# Main_Board_V2_0.net
KiCad netlist of a schematic drawn in EAGLE
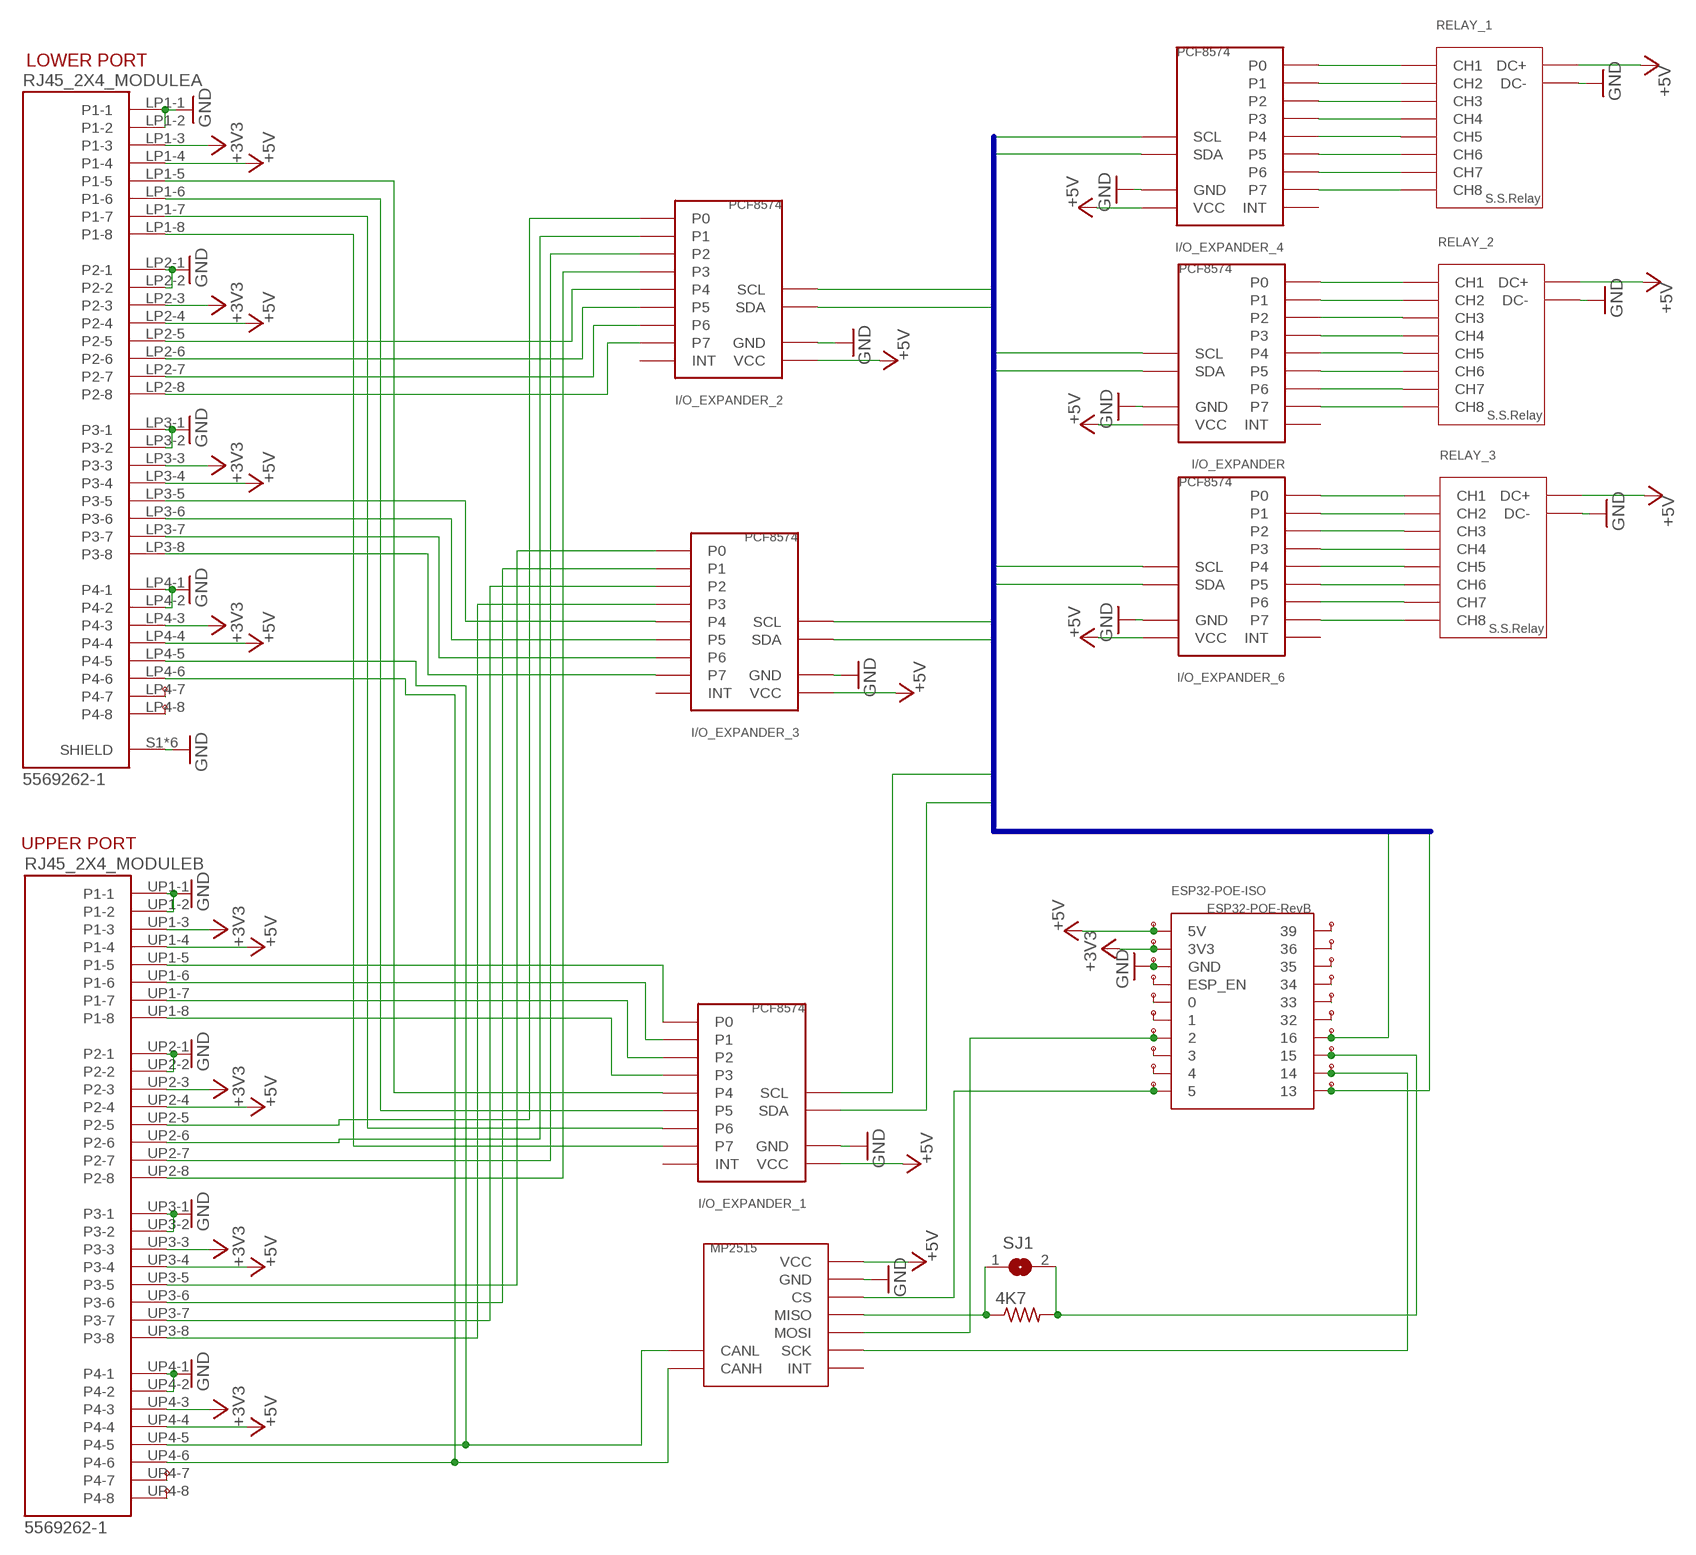
[diagram p0: schematic, sheet 1]

(export (version "E")
  (design (tool "Eeschema 10.0.6"))
  (components
    (comp (ref "4K7")
      (value "R-US_0207/10")
      (footprint "eagle-import:0207_10")
      (libsource (lib "eagle-import") (part "R-US_0207/10"))
    )
    (comp (ref "ESP32-POE-ISO")
      (value "ESP-POE")
      (footprint "eagle-import:ESP-POE")
      (libsource (lib "eagle-import") (part "ESP-POE"))
    )
    (comp (ref "I/O_EXPANDER")
      (value "PCF8574-MODULE_ESPELHADO")
      (footprint "eagle-import:PCF8574-MODULE_ESPELHADO")
      (libsource (lib "eagle-import") (part "PCF8574-MODULE_ESPELHADO"))
    )
    (comp (ref "I/O_EXPANDER_1")
      (value "PCF8574-MODULE_ESPELHADO")
      (footprint "eagle-import:PCF8574-MODULE_ESPELHADO")
      (libsource (lib "eagle-import") (part "PCF8574-MODULE_ESPELHADO"))
    )
    (comp (ref "I/O_EXPANDER_2")
      (value "PCF8574-MODULE_ESPELHADO")
      (footprint "eagle-import:PCF8574-MODULE_ESPELHADO")
      (libsource (lib "eagle-import") (part "PCF8574-MODULE_ESPELHADO"))
    )
    (comp (ref "I/O_EXPANDER_3")
      (value "PCF8574-MODULE_ESPELHADO")
      (footprint "eagle-import:PCF8574-MODULE_ESPELHADO")
      (libsource (lib "eagle-import") (part "PCF8574-MODULE_ESPELHADO"))
    )
    (comp (ref "I/O_EXPANDER_4")
      (value "PCF8574-MODULE_ESPELHADO")
      (footprint "eagle-import:PCF8574-MODULE_ESPELHADO")
      (libsource (lib "eagle-import") (part "PCF8574-MODULE_ESPELHADO"))
    )
    (comp (ref "I/O_EXPANDER_6")
      (value "PCF8574-MODULE_ESPELHADO")
      (footprint "eagle-import:PCF8574-MODULE_ESPELHADO")
      (libsource (lib "eagle-import") (part "PCF8574-MODULE_ESPELHADO"))
    )
    (comp (ref "RELAY_1")
      (value "SSR_M_FULL_SEM_LIGACOES")
      (footprint "eagle-import:SSR_M_SEM_LIGACOES")
      (libsource (lib "eagle-import") (part "SSR_M_FULL_SEM_LIGACOES"))
    )
    (comp (ref "RELAY_2")
      (value "SSR_M_FULL_SEM_LIGACOES")
      (footprint "eagle-import:SSR_M_SEM_LIGACOES")
      (libsource (lib "eagle-import") (part "SSR_M_FULL_SEM_LIGACOES"))
    )
    (comp (ref "RELAY_3")
      (value "SSR_M_FULL_SEM_LIGACOES")
      (footprint "eagle-import:SSR_M_SEM_LIGACOES")
      (libsource (lib "eagle-import") (part "SSR_M_FULL_SEM_LIGACOES"))
    )
    (comp (ref "RJ45_2X4_MODULE")
      (value "5569262-1")
      (footprint "eagle-import:TE_5569262-1")
      (fields (field (name "MF") "TE Connectivity"))
      (libsource (lib "eagle-import") (part "5569262-1"))
    )
    (comp (ref "SJ1") (value "SJ") (footprint "eagle-import:SJ") (libsource (lib "eagle-import") (part "SJ")))
    (comp (ref "U$1") (value "TP") (footprint "eagle-import:TP") (libsource (lib "eagle-import") (part "TP")))
    (comp (ref "U$2") (value "TP") (footprint "eagle-import:TP") (libsource (lib "eagle-import") (part "TP")))
    (comp (ref "U$4") (value "TP") (footprint "eagle-import:TP") (libsource (lib "eagle-import") (part "TP")))
    (comp (ref "U$5") (value "TP") (footprint "eagle-import:TP") (libsource (lib "eagle-import") (part "TP")))
    (comp (ref "U$6") (value "TP") (footprint "eagle-import:TP") (libsource (lib "eagle-import") (part "TP")))
    (comp (ref "U$7") (value "TP") (footprint "eagle-import:TP") (libsource (lib "eagle-import") (part "TP")))
    (comp (ref "U$8") (value "TP") (footprint "eagle-import:TP") (libsource (lib "eagle-import") (part "TP")))
    (comp (ref "U$9") (value "TP") (footprint "eagle-import:TP") (libsource (lib "eagle-import") (part "TP")))
    (comp (ref "U$10")
      (value "TP")
      (footprint "eagle-import:TP")
      (libsource (lib "eagle-import") (part "TP"))
    )
    (comp (ref "U$11")
      (value "TP")
      (footprint "eagle-import:TP")
      (libsource (lib "eagle-import") (part "TP"))
    )
    (comp (ref "U$12")
      (value "TP")
      (footprint "eagle-import:TP")
      (libsource (lib "eagle-import") (part "TP"))
    )
    (comp (ref "U$13")
      (value "TP")
      (footprint "eagle-import:TP")
      (libsource (lib "eagle-import") (part "TP"))
    )
    (comp (ref "U$14")
      (value "TP")
      (footprint "eagle-import:TP")
      (libsource (lib "eagle-import") (part "TP"))
    )
    (comp (ref "U$15")
      (value "TP")
      (footprint "eagle-import:TP")
      (libsource (lib "eagle-import") (part "TP"))
    )
    (comp (ref "U$16")
      (value "TP")
      (footprint "eagle-import:TP")
      (libsource (lib "eagle-import") (part "TP"))
    )
    (comp (ref "U$17")
      (value "TP")
      (footprint "eagle-import:TP")
      (libsource (lib "eagle-import") (part "TP"))
    )
    (comp (ref "U$18")
      (value "TP")
      (footprint "eagle-import:TP")
      (libsource (lib "eagle-import") (part "TP"))
    )
    (comp (ref "U$19")
      (value "TP")
      (footprint "eagle-import:TP")
      (libsource (lib "eagle-import") (part "TP"))
    )
    (comp (ref "U$20")
      (value "TP")
      (footprint "eagle-import:TP")
      (libsource (lib "eagle-import") (part "TP"))
    )
    (comp (ref "U$21")
      (value "TP")
      (footprint "eagle-import:TP")
      (libsource (lib "eagle-import") (part "TP"))
    )
    (comp (ref "U$22")
      (value "TP")
      (footprint "eagle-import:TP")
      (libsource (lib "eagle-import") (part "TP"))
    )
    (comp (ref "U$23")
      (value "TP")
      (footprint "eagle-import:TP")
      (libsource (lib "eagle-import") (part "TP"))
    )
    (comp (ref "U$24")
      (value "TP")
      (footprint "eagle-import:TP")
      (libsource (lib "eagle-import") (part "TP"))
    )
    (comp (ref "U$25")
      (value "TP")
      (footprint "eagle-import:TP")
      (libsource (lib "eagle-import") (part "TP"))
    )
    (comp (ref "U$26")
      (value "MCP2515_MODULE_SEM_LIGACOES")
      (footprint "eagle-import:MCP2515_MODULE_SEM_LIGACOES")
      (libsource (lib "eagle-import") (part "MCP2515_MODULE_SEM_LIGACOES"))
    )
  )
  (nets
    (net (code "1") (name "+3V3") (class "Default")
      (node (ref "ESP32-POE-ISO") (pin "3V3") (pinfunction "3V3_3V3") (pintype "bidirectional"))
      (node (ref "RJ45_2X4_MODULE") (pin "LP1-3") (pinfunction "P1-3_LP1-3") (pintype "passive"))
      (node (ref "RJ45_2X4_MODULE") (pin "LP2-3") (pinfunction "P2-3_LP2-3") (pintype "passive"))
      (node (ref "RJ45_2X4_MODULE") (pin "LP3-3") (pinfunction "P3-3_LP3-3") (pintype "passive"))
      (node (ref "RJ45_2X4_MODULE") (pin "LP4-3") (pinfunction "P4-3_LP4-3") (pintype "passive"))
      (node (ref "RJ45_2X4_MODULE") (pin "UP1-3") (pinfunction "P1-3_UP1-3") (pintype "passive"))
      (node (ref "RJ45_2X4_MODULE") (pin "UP2-3") (pinfunction "P2-3_UP2-3") (pintype "passive"))
      (node (ref "RJ45_2X4_MODULE") (pin "UP3-3") (pinfunction "P3-3_UP3-3") (pintype "passive"))
      (node (ref "RJ45_2X4_MODULE") (pin "UP4-3") (pinfunction "P4-3_UP4-3") (pintype "passive"))
      (node (ref "U$6") (pin "P$1") (pinfunction "P$1_P$1") (pintype "bidirectional"))
    )
    (net (code "2") (name "+5V") (class "Default")
      (node (ref "ESP32-POE-ISO") (pin "5V") (pinfunction "5V_5V") (pintype "bidirectional"))
      (node (ref "I/O_EXPANDER") (pin "VCC") (pinfunction "VCC_VCC") (pintype "bidirectional"))
      (node (ref "I/O_EXPANDER_1") (pin "VCC") (pinfunction "VCC_VCC") (pintype "bidirectional"))
      (node (ref "I/O_EXPANDER_2") (pin "VCC") (pinfunction "VCC_VCC") (pintype "bidirectional"))
      (node (ref "I/O_EXPANDER_3") (pin "VCC") (pinfunction "VCC_VCC") (pintype "bidirectional"))
      (node (ref "I/O_EXPANDER_4") (pin "VCC") (pinfunction "VCC_VCC") (pintype "bidirectional"))
      (node (ref "I/O_EXPANDER_6") (pin "VCC") (pinfunction "VCC_VCC") (pintype "bidirectional"))
      (node (ref "RELAY_1") (pin "DC+") (pinfunction "DC+_DC+") (pintype "bidirectional"))
      (node (ref "RELAY_2") (pin "DC+") (pinfunction "DC+_DC+") (pintype "bidirectional"))
      (node (ref "RELAY_3") (pin "DC+") (pinfunction "DC+_DC+") (pintype "bidirectional"))
      (node (ref "RJ45_2X4_MODULE") (pin "LP1-4") (pinfunction "P1-4_LP1-4") (pintype "passive"))
      (node (ref "RJ45_2X4_MODULE") (pin "LP2-4") (pinfunction "P2-4_LP2-4") (pintype "passive"))
      (node (ref "RJ45_2X4_MODULE") (pin "LP3-4") (pinfunction "P3-4_LP3-4") (pintype "passive"))
      (node (ref "RJ45_2X4_MODULE") (pin "LP4-4") (pinfunction "P4-4_LP4-4") (pintype "passive"))
      (node (ref "RJ45_2X4_MODULE") (pin "UP1-4") (pinfunction "P1-4_UP1-4") (pintype "passive"))
      (node (ref "RJ45_2X4_MODULE") (pin "UP2-4") (pinfunction "P2-4_UP2-4") (pintype "passive"))
      (node (ref "RJ45_2X4_MODULE") (pin "UP3-4") (pinfunction "P3-4_UP3-4") (pintype "passive"))
      (node (ref "RJ45_2X4_MODULE") (pin "UP4-4") (pinfunction "P4-4_UP4-4") (pintype "passive"))
      (node (ref "U$2") (pin "P$1") (pinfunction "P$1_P$1") (pintype "bidirectional"))
      (node (ref "U$26") (pin "VCC") (pinfunction "VCC_VCC") (pintype "bidirectional"))
    )
    (net (code "3") (name "/SCL") (class "Default")
      (node (ref "ESP32-POE-ISO") (pin "16") (pinfunction "16_16") (pintype "bidirectional"))
      (node (ref "I/O_EXPANDER") (pin "SCL") (pinfunction "SCL_SCL") (pintype "bidirectional"))
      (node (ref "I/O_EXPANDER_1") (pin "SCL") (pinfunction "SCL_SCL") (pintype "bidirectional"))
      (node (ref "I/O_EXPANDER_2") (pin "SCL") (pinfunction "SCL_SCL") (pintype "bidirectional"))
      (node (ref "I/O_EXPANDER_3") (pin "SCL") (pinfunction "SCL_SCL") (pintype "bidirectional"))
      (node (ref "I/O_EXPANDER_4") (pin "SCL") (pinfunction "SCL_SCL") (pintype "bidirectional"))
      (node (ref "I/O_EXPANDER_6") (pin "SCL") (pinfunction "SCL_SCL") (pintype "bidirectional"))
      (node (ref "U$21") (pin "P$1") (pinfunction "P$1_P$1") (pintype "bidirectional"))
    )
    (net (code "4") (name "/SDA") (class "Default")
      (node (ref "ESP32-POE-ISO") (pin "13") (pinfunction "13_13") (pintype "bidirectional"))
      (node (ref "I/O_EXPANDER") (pin "SDA") (pinfunction "SDA_SDA") (pintype "bidirectional"))
      (node (ref "I/O_EXPANDER_1") (pin "SDA") (pinfunction "SDA_SDA") (pintype "bidirectional"))
      (node (ref "I/O_EXPANDER_2") (pin "SDA") (pinfunction "SDA_SDA") (pintype "bidirectional"))
      (node (ref "I/O_EXPANDER_3") (pin "SDA") (pinfunction "SDA_SDA") (pintype "bidirectional"))
      (node (ref "I/O_EXPANDER_4") (pin "SDA") (pinfunction "SDA_SDA") (pintype "bidirectional"))
      (node (ref "I/O_EXPANDER_6") (pin "SDA") (pinfunction "SDA_SDA") (pintype "bidirectional"))
      (node (ref "U$24") (pin "P$1") (pinfunction "P$1_P$1") (pintype "bidirectional"))
    )
    (net (code "5") (name "GND") (class "Default")
      (node (ref "ESP32-POE-ISO") (pin "GND") (pinfunction "GND_GND") (pintype "bidirectional"))
      (node (ref "I/O_EXPANDER") (pin "GND") (pinfunction "GND_GND") (pintype "bidirectional"))
      (node (ref "I/O_EXPANDER_1") (pin "GND") (pinfunction "GND_GND") (pintype "bidirectional"))
      (node (ref "I/O_EXPANDER_2") (pin "GND") (pinfunction "GND_GND") (pintype "bidirectional"))
      (node (ref "I/O_EXPANDER_3") (pin "GND") (pinfunction "GND_GND") (pintype "bidirectional"))
      (node (ref "I/O_EXPANDER_4") (pin "GND") (pinfunction "GND_GND") (pintype "bidirectional"))
      (node (ref "I/O_EXPANDER_6") (pin "GND") (pinfunction "GND_GND") (pintype "bidirectional"))
      (node (ref "RELAY_1") (pin "DC-") (pinfunction "DC-_DC-") (pintype "bidirectional"))
      (node (ref "RELAY_2") (pin "DC-") (pinfunction "DC-_DC-") (pintype "bidirectional"))
      (node (ref "RELAY_3") (pin "DC-") (pinfunction "DC-_DC-") (pintype "bidirectional"))
      (node (ref "RJ45_2X4_MODULE") (pin "LP1-1") (pinfunction "P1-1_LP1-1") (pintype "passive"))
      (node (ref "RJ45_2X4_MODULE") (pin "LP1-2") (pinfunction "P1-2_LP1-2") (pintype "passive"))
      (node (ref "RJ45_2X4_MODULE") (pin "LP2-1") (pinfunction "P2-1_LP2-1") (pintype "passive"))
      (node (ref "RJ45_2X4_MODULE") (pin "LP2-2") (pinfunction "P2-2_LP2-2") (pintype "passive"))
      (node (ref "RJ45_2X4_MODULE") (pin "LP3-1") (pinfunction "P3-1_LP3-1") (pintype "passive"))
      (node (ref "RJ45_2X4_MODULE") (pin "LP3-2") (pinfunction "P3-2_LP3-2") (pintype "passive"))
      (node (ref "RJ45_2X4_MODULE") (pin "LP4-1") (pinfunction "P4-1_LP4-1") (pintype "passive"))
      (node (ref "RJ45_2X4_MODULE") (pin "LP4-2") (pinfunction "P4-2_LP4-2") (pintype "passive"))
      (node (ref "RJ45_2X4_MODULE") (pin "S1") (pinfunction "SHIELD_S1") (pintype "passive"))
      (node (ref "RJ45_2X4_MODULE") (pin "S2") (pinfunction "SHIELD_S2") (pintype "passive"))
      (node (ref "RJ45_2X4_MODULE") (pin "S3") (pinfunction "SHIELD_S3") (pintype "passive"))
      (node (ref "RJ45_2X4_MODULE") (pin "S4") (pinfunction "SHIELD_S4") (pintype "passive"))
      (node (ref "RJ45_2X4_MODULE") (pin "S5") (pinfunction "SHIELD_S5") (pintype "passive"))
      (node (ref "RJ45_2X4_MODULE") (pin "S6") (pinfunction "SHIELD_S6") (pintype "passive"))
      (node (ref "RJ45_2X4_MODULE") (pin "UP1-1") (pinfunction "P1-1_UP1-1") (pintype "passive"))
      (node (ref "RJ45_2X4_MODULE") (pin "UP1-2") (pinfunction "P1-2_UP1-2") (pintype "passive"))
      (node (ref "RJ45_2X4_MODULE") (pin "UP2-1") (pinfunction "P2-1_UP2-1") (pintype "passive"))
      (node (ref "RJ45_2X4_MODULE") (pin "UP2-2") (pinfunction "P2-2_UP2-2") (pintype "passive"))
      (node (ref "RJ45_2X4_MODULE") (pin "UP3-1") (pinfunction "P3-1_UP3-1") (pintype "passive"))
      (node (ref "RJ45_2X4_MODULE") (pin "UP3-2") (pinfunction "P3-2_UP3-2") (pintype "passive"))
      (node (ref "RJ45_2X4_MODULE") (pin "UP4-1") (pinfunction "P4-1_UP4-1") (pintype "passive"))
      (node (ref "RJ45_2X4_MODULE") (pin "UP4-2") (pinfunction "P4-2_UP4-2") (pintype "passive"))
      (node (ref "U$26") (pin "GND") (pinfunction "GND_GND") (pintype "bidirectional"))
      (node (ref "U$7") (pin "P$1") (pinfunction "P$1_P$1") (pintype "bidirectional"))
    )
    (net (code "6") (name "Net-(4K7-Pad1)") (class "Default")
      (node (ref "4K7") (pin "1") (pinfunction "1_1") (pintype "passive"))
      (node (ref "SJ1") (pin "1") (pinfunction "1_1") (pintype "passive"))
      (node (ref "U$26") (pin "MISO") (pinfunction "MISO_MISO") (pintype "bidirectional"))
    )
    (net (code "7") (name "Net-(4K7-Pad2)") (class "Default")
      (node (ref "4K7") (pin "2") (pinfunction "2_2") (pintype "passive"))
      (node (ref "ESP32-POE-ISO") (pin "15") (pinfunction "15_15") (pintype "bidirectional"))
      (node (ref "SJ1") (pin "2") (pinfunction "2_2") (pintype "passive"))
      (node (ref "U$22") (pin "P$1") (pinfunction "P$1_P$1") (pintype "bidirectional"))
    )
    (net (code "8") (name "Net-(ESP32-POE-ISO-Pad0)") (class "Default")
      (node (ref "ESP32-POE-ISO") (pin "0") (pinfunction "0_0") (pintype "bidirectional"))
      (node (ref "U$9") (pin "P$1") (pinfunction "P$1_P$1") (pintype "bidirectional"))
    )
    (net (code "9") (name "Net-(ESP32-POE-ISO-Pad1)") (class "Default")
      (node (ref "ESP32-POE-ISO") (pin "1") (pinfunction "1_1") (pintype "bidirectional"))
      (node (ref "U$10") (pin "P$1") (pinfunction "P$1_P$1") (pintype "bidirectional"))
    )
    (net (code "10") (name "Net-(ESP32-POE-ISO-Pad2)") (class "Default")
      (node (ref "ESP32-POE-ISO") (pin "2") (pinfunction "2_2") (pintype "bidirectional"))
      (node (ref "U$11") (pin "P$1") (pinfunction "P$1_P$1") (pintype "bidirectional"))
      (node (ref "U$26") (pin "MOSI") (pinfunction "MOSI_MOSI") (pintype "bidirectional"))
    )
    (net (code "11") (name "Net-(ESP32-POE-ISO-Pad3)") (class "Default")
      (node (ref "ESP32-POE-ISO") (pin "3") (pinfunction "3_3") (pintype "bidirectional"))
      (node (ref "U$12") (pin "P$1") (pinfunction "P$1_P$1") (pintype "bidirectional"))
    )
    (net (code "12") (name "Net-(ESP32-POE-ISO-Pad4)") (class "Default")
      (node (ref "ESP32-POE-ISO") (pin "4") (pinfunction "4_4") (pintype "bidirectional"))
      (node (ref "U$13") (pin "P$1") (pinfunction "P$1_P$1") (pintype "bidirectional"))
    )
    (net (code "13") (name "Net-(ESP32-POE-ISO-Pad5)") (class "Default")
      (node (ref "ESP32-POE-ISO") (pin "5") (pinfunction "5_5") (pintype "bidirectional"))
      (node (ref "U$14") (pin "P$1") (pinfunction "P$1_P$1") (pintype "bidirectional"))
      (node (ref "U$26") (pin "CS") (pinfunction "CS_CS") (pintype "bidirectional"))
    )
    (net (code "14") (name "Net-(ESP32-POE-ISO-Pad14)") (class "Default")
      (node (ref "ESP32-POE-ISO") (pin "14") (pinfunction "14_14") (pintype "bidirectional"))
      (node (ref "U$23") (pin "P$1") (pinfunction "P$1_P$1") (pintype "bidirectional"))
      (node (ref "U$26") (pin "SCK") (pinfunction "SCK_SCK") (pintype "bidirectional"))
    )
    (net (code "15") (name "Net-(ESP32-POE-ISO-Pad32)") (class "Default")
      (node (ref "ESP32-POE-ISO") (pin "32") (pinfunction "32_32") (pintype "bidirectional"))
      (node (ref "U$20") (pin "P$1") (pinfunction "P$1_P$1") (pintype "bidirectional"))
    )
    (net (code "16") (name "Net-(ESP32-POE-ISO-Pad33)") (class "Default")
      (node (ref "ESP32-POE-ISO") (pin "33") (pinfunction "33_33") (pintype "bidirectional"))
      (node (ref "U$19") (pin "P$1") (pinfunction "P$1_P$1") (pintype "bidirectional"))
    )
    (net (code "17") (name "Net-(ESP32-POE-ISO-Pad34)") (class "Default")
      (node (ref "ESP32-POE-ISO") (pin "34") (pinfunction "34_34") (pintype "bidirectional"))
      (node (ref "U$18") (pin "P$1") (pinfunction "P$1_P$1") (pintype "bidirectional"))
    )
    (net (code "18") (name "Net-(ESP32-POE-ISO-Pad35)") (class "Default")
      (node (ref "ESP32-POE-ISO") (pin "35") (pinfunction "35_35") (pintype "bidirectional"))
      (node (ref "U$17") (pin "P$1") (pinfunction "P$1_P$1") (pintype "bidirectional"))
    )
    (net (code "19") (name "Net-(ESP32-POE-ISO-Pad36)") (class "Default")
      (node (ref "ESP32-POE-ISO") (pin "36") (pinfunction "36_36") (pintype "bidirectional"))
      (node (ref "U$16") (pin "P$1") (pinfunction "P$1_P$1") (pintype "bidirectional"))
    )
    (net (code "20") (name "Net-(ESP32-POE-ISO-Pad39)") (class "Default")
      (node (ref "ESP32-POE-ISO") (pin "39") (pinfunction "39_39") (pintype "bidirectional"))
      (node (ref "U$15") (pin "P$1") (pinfunction "P$1_P$1") (pintype "bidirectional"))
    )
    (net (code "21") (name "Net-(ESP32-POE-ISO-PadESP_EN)") (class "Default")
      (node (ref "ESP32-POE-ISO") (pin "ESP_EN") (pinfunction "ESP_EN_ESP_EN") (pintype "bidirectional"))
      (node (ref "U$8") (pin "P$1") (pinfunction "P$1_P$1") (pintype "bidirectional"))
    )
    (net (code "22") (name "Net-(I/O_EXPANDER-PadP0)") (class "Default")
      (node (ref "I/O_EXPANDER") (pin "P0") (pinfunction "P0_P0") (pintype "bidirectional"))
      (node (ref "RELAY_2") (pin "CH1") (pinfunction "CH1_CH1") (pintype "bidirectional"))
    )
    (net (code "23") (name "Net-(I/O_EXPANDER-PadP1)") (class "Default")
      (node (ref "I/O_EXPANDER") (pin "P1") (pinfunction "P1_P1") (pintype "bidirectional"))
      (node (ref "RELAY_2") (pin "CH2") (pinfunction "CH2_CH2") (pintype "bidirectional"))
    )
    (net (code "24") (name "Net-(I/O_EXPANDER-PadP2)") (class "Default")
      (node (ref "I/O_EXPANDER") (pin "P2") (pinfunction "P2_P2") (pintype "bidirectional"))
      (node (ref "RELAY_2") (pin "CH3") (pinfunction "CH3_CH3") (pintype "bidirectional"))
    )
    (net (code "25") (name "Net-(I/O_EXPANDER-PadP3)") (class "Default")
      (node (ref "I/O_EXPANDER") (pin "P3") (pinfunction "P3_P3") (pintype "bidirectional"))
      (node (ref "RELAY_2") (pin "CH4") (pinfunction "CH4_CH4") (pintype "bidirectional"))
    )
    (net (code "26") (name "Net-(I/O_EXPANDER-PadP4)") (class "Default")
      (node (ref "I/O_EXPANDER") (pin "P4") (pinfunction "P4_P4") (pintype "bidirectional"))
      (node (ref "RELAY_2") (pin "CH5") (pinfunction "CH5_CH5") (pintype "bidirectional"))
    )
    (net (code "27") (name "Net-(I/O_EXPANDER-PadP5)") (class "Default")
      (node (ref "I/O_EXPANDER") (pin "P5") (pinfunction "P5_P5") (pintype "bidirectional"))
      (node (ref "RELAY_2") (pin "CH6") (pinfunction "CH6_CH6") (pintype "bidirectional"))
    )
    (net (code "28") (name "Net-(I/O_EXPANDER-PadP6)") (class "Default")
      (node (ref "I/O_EXPANDER") (pin "P6") (pinfunction "P6_P6") (pintype "bidirectional"))
      (node (ref "RELAY_2") (pin "CH7") (pinfunction "CH7_CH7") (pintype "bidirectional"))
    )
    (net (code "29") (name "Net-(I/O_EXPANDER-PadP7)") (class "Default")
      (node (ref "I/O_EXPANDER") (pin "P7") (pinfunction "P7_P7") (pintype "bidirectional"))
      (node (ref "RELAY_2") (pin "CH8") (pinfunction "CH8_CH8") (pintype "bidirectional"))
    )
    (net (code "30") (name "Net-(I/O_EXPANDER_4-PadP0)") (class "Default")
      (node (ref "I/O_EXPANDER_4") (pin "P0") (pinfunction "P0_P0") (pintype "bidirectional"))
      (node (ref "RELAY_1") (pin "CH1") (pinfunction "CH1_CH1") (pintype "bidirectional"))
    )
    (net (code "31") (name "Net-(I/O_EXPANDER_4-PadP1)") (class "Default")
      (node (ref "I/O_EXPANDER_4") (pin "P1") (pinfunction "P1_P1") (pintype "bidirectional"))
      (node (ref "RELAY_1") (pin "CH2") (pinfunction "CH2_CH2") (pintype "bidirectional"))
    )
    (net (code "32") (name "Net-(I/O_EXPANDER_4-PadP2)") (class "Default")
      (node (ref "I/O_EXPANDER_4") (pin "P2") (pinfunction "P2_P2") (pintype "bidirectional"))
      (node (ref "RELAY_1") (pin "CH3") (pinfunction "CH3_CH3") (pintype "bidirectional"))
    )
    (net (code "33") (name "Net-(I/O_EXPANDER_4-PadP3)") (class "Default")
      (node (ref "I/O_EXPANDER_4") (pin "P3") (pinfunction "P3_P3") (pintype "bidirectional"))
      (node (ref "RELAY_1") (pin "CH4") (pinfunction "CH4_CH4") (pintype "bidirectional"))
    )
    (net (code "34") (name "Net-(I/O_EXPANDER_4-PadP4)") (class "Default")
      (node (ref "I/O_EXPANDER_4") (pin "P4") (pinfunction "P4_P4") (pintype "bidirectional"))
      (node (ref "RELAY_1") (pin "CH5") (pinfunction "CH5_CH5") (pintype "bidirectional"))
    )
    (net (code "35") (name "Net-(I/O_EXPANDER_4-PadP5)") (class "Default")
      (node (ref "I/O_EXPANDER_4") (pin "P5") (pinfunction "P5_P5") (pintype "bidirectional"))
      (node (ref "RELAY_1") (pin "CH6") (pinfunction "CH6_CH6") (pintype "bidirectional"))
    )
    (net (code "36") (name "Net-(I/O_EXPANDER_4-PadP6)") (class "Default")
      (node (ref "I/O_EXPANDER_4") (pin "P6") (pinfunction "P6_P6") (pintype "bidirectional"))
      (node (ref "RELAY_1") (pin "CH7") (pinfunction "CH7_CH7") (pintype "bidirectional"))
    )
    (net (code "37") (name "Net-(I/O_EXPANDER_4-PadP7)") (class "Default")
      (node (ref "I/O_EXPANDER_4") (pin "P7") (pinfunction "P7_P7") (pintype "bidirectional"))
      (node (ref "RELAY_1") (pin "CH8") (pinfunction "CH8_CH8") (pintype "bidirectional"))
    )
    (net (code "38") (name "Net-(I/O_EXPANDER_6-PadP0)") (class "Default")
      (node (ref "I/O_EXPANDER_6") (pin "P0") (pinfunction "P0_P0") (pintype "bidirectional"))
      (node (ref "RELAY_3") (pin "CH1") (pinfunction "CH1_CH1") (pintype "bidirectional"))
    )
    (net (code "39") (name "Net-(I/O_EXPANDER_6-PadP1)") (class "Default")
      (node (ref "I/O_EXPANDER_6") (pin "P1") (pinfunction "P1_P1") (pintype "bidirectional"))
      (node (ref "RELAY_3") (pin "CH2") (pinfunction "CH2_CH2") (pintype "bidirectional"))
    )
    (net (code "40") (name "Net-(I/O_EXPANDER_6-PadP2)") (class "Default")
      (node (ref "I/O_EXPANDER_6") (pin "P2") (pinfunction "P2_P2") (pintype "bidirectional"))
      (node (ref "RELAY_3") (pin "CH3") (pinfunction "CH3_CH3") (pintype "bidirectional"))
    )
    (net (code "41") (name "Net-(I/O_EXPANDER_6-PadP3)") (class "Default")
      (node (ref "I/O_EXPANDER_6") (pin "P3") (pinfunction "P3_P3") (pintype "bidirectional"))
      (node (ref "RELAY_3") (pin "CH4") (pinfunction "CH4_CH4") (pintype "bidirectional"))
    )
    (net (code "42") (name "Net-(I/O_EXPANDER_6-PadP4)") (class "Default")
      (node (ref "I/O_EXPANDER_6") (pin "P4") (pinfunction "P4_P4") (pintype "bidirectional"))
      (node (ref "RELAY_3") (pin "CH5") (pinfunction "CH5_CH5") (pintype "bidirectional"))
    )
    (net (code "43") (name "Net-(I/O_EXPANDER_6-PadP5)") (class "Default")
      (node (ref "I/O_EXPANDER_6") (pin "P5") (pinfunction "P5_P5") (pintype "bidirectional"))
      (node (ref "RELAY_3") (pin "CH6") (pinfunction "CH6_CH6") (pintype "bidirectional"))
    )
    (net (code "44") (name "Net-(I/O_EXPANDER_6-PadP6)") (class "Default")
      (node (ref "I/O_EXPANDER_6") (pin "P6") (pinfunction "P6_P6") (pintype "bidirectional"))
      (node (ref "RELAY_3") (pin "CH7") (pinfunction "CH7_CH7") (pintype "bidirectional"))
    )
    (net (code "45") (name "Net-(I/O_EXPANDER_6-PadP7)") (class "Default")
      (node (ref "I/O_EXPANDER_6") (pin "P7") (pinfunction "P7_P7") (pintype "bidirectional"))
      (node (ref "RELAY_3") (pin "CH8") (pinfunction "CH8_CH8") (pintype "bidirectional"))
    )
    (net (code "46") (name "Net-(RJ45_2X4_MODULEA-P1-5)") (class "Default")
      (node (ref "I/O_EXPANDER_1") (pin "P4") (pinfunction "P4_P4") (pintype "bidirectional"))
      (node (ref "RJ45_2X4_MODULE") (pin "LP1-5") (pinfunction "P1-5_LP1-5") (pintype "passive"))
    )
    (net (code "47") (name "Net-(RJ45_2X4_MODULEA-P1-6)") (class "Default")
      (node (ref "I/O_EXPANDER_1") (pin "P5") (pinfunction "P5_P5") (pintype "bidirectional"))
      (node (ref "RJ45_2X4_MODULE") (pin "LP1-6") (pinfunction "P1-6_LP1-6") (pintype "passive"))
    )
    (net (code "48") (name "Net-(RJ45_2X4_MODULEA-P1-7)") (class "Default")
      (node (ref "I/O_EXPANDER_1") (pin "P6") (pinfunction "P6_P6") (pintype "bidirectional"))
      (node (ref "RJ45_2X4_MODULE") (pin "LP1-7") (pinfunction "P1-7_LP1-7") (pintype "passive"))
    )
    (net (code "49") (name "Net-(RJ45_2X4_MODULEA-P1-8)") (class "Default")
      (node (ref "I/O_EXPANDER_1") (pin "P7") (pinfunction "P7_P7") (pintype "bidirectional"))
      (node (ref "RJ45_2X4_MODULE") (pin "LP1-8") (pinfunction "P1-8_LP1-8") (pintype "passive"))
    )
    (net (code "50") (name "Net-(RJ45_2X4_MODULEA-P2-5)") (class "Default")
      (node (ref "I/O_EXPANDER_2") (pin "P4") (pinfunction "P4_P4") (pintype "bidirectional"))
      (node (ref "RJ45_2X4_MODULE") (pin "LP2-5") (pinfunction "P2-5_LP2-5") (pintype "passive"))
    )
    (net (code "51") (name "Net-(RJ45_2X4_MODULEA-P2-6)") (class "Default")
      (node (ref "I/O_EXPANDER_2") (pin "P5") (pinfunction "P5_P5") (pintype "bidirectional"))
      (node (ref "RJ45_2X4_MODULE") (pin "LP2-6") (pinfunction "P2-6_LP2-6") (pintype "passive"))
    )
    (net (code "52") (name "Net-(RJ45_2X4_MODULEA-P2-7)") (class "Default")
      (node (ref "I/O_EXPANDER_2") (pin "P6") (pinfunction "P6_P6") (pintype "bidirectional"))
      (node (ref "RJ45_2X4_MODULE") (pin "LP2-7") (pinfunction "P2-7_LP2-7") (pintype "passive"))
    )
    (net (code "53") (name "Net-(RJ45_2X4_MODULEA-P2-8)") (class "Default")
      (node (ref "I/O_EXPANDER_2") (pin "P7") (pinfunction "P7_P7") (pintype "bidirectional"))
      (node (ref "RJ45_2X4_MODULE") (pin "LP2-8") (pinfunction "P2-8_LP2-8") (pintype "passive"))
    )
    (net (code "54") (name "Net-(RJ45_2X4_MODULEA-P3-5)") (class "Default")
      (node (ref "I/O_EXPANDER_3") (pin "P4") (pinfunction "P4_P4") (pintype "bidirectional"))
      (node (ref "RJ45_2X4_MODULE") (pin "LP3-5") (pinfunction "P3-5_LP3-5") (pintype "passive"))
    )
    (net (code "55") (name "Net-(RJ45_2X4_MODULEA-P3-6)") (class "Default")
      (node (ref "I/O_EXPANDER_3") (pin "P5") (pinfunction "P5_P5") (pintype "bidirectional"))
      (node (ref "RJ45_2X4_MODULE") (pin "LP3-6") (pinfunction "P3-6_LP3-6") (pintype "passive"))
    )
    (net (code "56") (name "Net-(RJ45_2X4_MODULEA-P3-7)") (class "Default")
      (node (ref "I/O_EXPANDER_3") (pin "P6") (pinfunction "P6_P6") (pintype "bidirectional"))
      (node (ref "RJ45_2X4_MODULE") (pin "LP3-7") (pinfunction "P3-7_LP3-7") (pintype "passive"))
    )
    (net (code "57") (name "Net-(RJ45_2X4_MODULEA-P3-8)") (class "Default")
      (node (ref "I/O_EXPANDER_3") (pin "P7") (pinfunction "P7_P7") (pintype "bidirectional"))
      (node (ref "RJ45_2X4_MODULE") (pin "LP3-8") (pinfunction "P3-8_LP3-8") (pintype "passive"))
    )
    (net (code "58") (name "Net-(RJ45_2X4_MODULEA-P4-5)") (class "Default")
      (node (ref "RJ45_2X4_MODULE") (pin "LP4-5") (pinfunction "P4-5_LP4-5") (pintype "passive"))
      (node (ref "RJ45_2X4_MODULE") (pin "UP4-5") (pinfunction "P4-5_UP4-5") (pintype "passive"))
      (node (ref "U$26") (pin "CL") (pinfunction "CANL_CL") (pintype "bidirectional"))
    )
    (net (code "59") (name "Net-(RJ45_2X4_MODULEA-P4-6)") (class "Default")
      (node (ref "RJ45_2X4_MODULE") (pin "LP4-6") (pinfunction "P4-6_LP4-6") (pintype "passive"))
      (node (ref "RJ45_2X4_MODULE") (pin "UP4-6") (pinfunction "P4-6_UP4-6") (pintype "passive"))
      (node (ref "U$26") (pin "CH") (pinfunction "CANH_CH") (pintype "bidirectional"))
    )
    (net (code "60") (name "Net-(RJ45_2X4_MODULEA-P4-7)") (class "Default")
      (node (ref "RJ45_2X4_MODULE") (pin "LP4-7") (pinfunction "P4-7_LP4-7") (pintype "passive"))
      (node (ref "U$5") (pin "P$1") (pinfunction "P$1_P$1") (pintype "bidirectional"))
    )
    (net (code "61") (name "Net-(RJ45_2X4_MODULEA-P4-8)") (class "Default")
      (node (ref "RJ45_2X4_MODULE") (pin "LP4-8") (pinfunction "P4-8_LP4-8") (pintype "passive"))
      (node (ref "U$25") (pin "P$1") (pinfunction "P$1_P$1") (pintype "bidirectional"))
    )
    (net (code "62") (name "Net-(RJ45_2X4_MODULEB-P1-5)") (class "Default")
      (node (ref "I/O_EXPANDER_1") (pin "P0") (pinfunction "P0_P0") (pintype "bidirectional"))
      (node (ref "RJ45_2X4_MODULE") (pin "UP1-5") (pinfunction "P1-5_UP1-5") (pintype "passive"))
    )
    (net (code "63") (name "Net-(RJ45_2X4_MODULEB-P1-6)") (class "Default")
      (node (ref "I/O_EXPANDER_1") (pin "P1") (pinfunction "P1_P1") (pintype "bidirectional"))
      (node (ref "RJ45_2X4_MODULE") (pin "UP1-6") (pinfunction "P1-6_UP1-6") (pintype "passive"))
    )
    (net (code "64") (name "Net-(RJ45_2X4_MODULEB-P1-7)") (class "Default")
      (node (ref "I/O_EXPANDER_1") (pin "P2") (pinfunction "P2_P2") (pintype "bidirectional"))
      (node (ref "RJ45_2X4_MODULE") (pin "UP1-7") (pinfunction "P1-7_UP1-7") (pintype "passive"))
    )
    (net (code "65") (name "Net-(RJ45_2X4_MODULEB-P1-8)") (class "Default")
      (node (ref "I/O_EXPANDER_1") (pin "P3") (pinfunction "P3_P3") (pintype "bidirectional"))
      (node (ref "RJ45_2X4_MODULE") (pin "UP1-8") (pinfunction "P1-8_UP1-8") (pintype "passive"))
    )
    (net (code "66") (name "Net-(RJ45_2X4_MODULEB-P2-5)") (class "Default")
      (node (ref "I/O_EXPANDER_2") (pin "P0") (pinfunction "P0_P0") (pintype "bidirectional"))
      (node (ref "RJ45_2X4_MODULE") (pin "UP2-5") (pinfunction "P2-5_UP2-5") (pintype "passive"))
    )
    (net (code "67") (name "Net-(RJ45_2X4_MODULEB-P2-6)") (class "Default")
      (node (ref "I/O_EXPANDER_2") (pin "P1") (pinfunction "P1_P1") (pintype "bidirectional"))
      (node (ref "RJ45_2X4_MODULE") (pin "UP2-6") (pinfunction "P2-6_UP2-6") (pintype "passive"))
    )
    (net (code "68") (name "Net-(RJ45_2X4_MODULEB-P2-7)") (class "Default")
      (node (ref "I/O_EXPANDER_2") (pin "P2") (pinfunction "P2_P2") (pintype "bidirectional"))
      (node (ref "RJ45_2X4_MODULE") (pin "UP2-7") (pinfunction "P2-7_UP2-7") (pintype "passive"))
    )
    (net (code "69") (name "Net-(RJ45_2X4_MODULEB-P2-8)") (class "Default")
      (node (ref "I/O_EXPANDER_2") (pin "P3") (pinfunction "P3_P3") (pintype "bidirectional"))
      (node (ref "RJ45_2X4_MODULE") (pin "UP2-8") (pinfunction "P2-8_UP2-8") (pintype "passive"))
    )
    (net (code "70") (name "Net-(RJ45_2X4_MODULEB-P3-5)") (class "Default")
      (node (ref "I/O_EXPANDER_3") (pin "P0") (pinfunction "P0_P0") (pintype "bidirectional"))
      (node (ref "RJ45_2X4_MODULE") (pin "UP3-5") (pinfunction "P3-5_UP3-5") (pintype "passive"))
    )
    (net (code "71") (name "Net-(RJ45_2X4_MODULEB-P3-6)") (class "Default")
      (node (ref "I/O_EXPANDER_3") (pin "P1") (pinfunction "P1_P1") (pintype "bidirectional"))
      (node (ref "RJ45_2X4_MODULE") (pin "UP3-6") (pinfunction "P3-6_UP3-6") (pintype "passive"))
    )
    (net (code "72") (name "Net-(RJ45_2X4_MODULEB-P3-7)") (class "Default")
      (node (ref "I/O_EXPANDER_3") (pin "P2") (pinfunction "P2_P2") (pintype "bidirectional"))
      (node (ref "RJ45_2X4_MODULE") (pin "UP3-7") (pinfunction "P3-7_UP3-7") (pintype "passive"))
    )
    (net (code "73") (name "Net-(RJ45_2X4_MODULEB-P3-8)") (class "Default")
      (node (ref "I/O_EXPANDER_3") (pin "P3") (pinfunction "P3_P3") (pintype "bidirectional"))
      (node (ref "RJ45_2X4_MODULE") (pin "UP3-8") (pinfunction "P3-8_UP3-8") (pintype "passive"))
    )
    (net (code "74") (name "Net-(RJ45_2X4_MODULEB-P4-7)") (class "Default")
      (node (ref "RJ45_2X4_MODULE") (pin "UP4-7") (pinfunction "P4-7_UP4-7") (pintype "passive"))
      (node (ref "U$1") (pin "P$1") (pinfunction "P$1_P$1") (pintype "bidirectional"))
    )
    (net (code "75") (name "Net-(RJ45_2X4_MODULEB-P4-8)") (class "Default")
      (node (ref "RJ45_2X4_MODULE") (pin "UP4-8") (pinfunction "P4-8_UP4-8") (pintype "passive"))
      (node (ref "U$4") (pin "P$1") (pinfunction "P$1_P$1") (pintype "bidirectional"))
    )
    (net (code "76") (name "unconnected-(I/O_EXPANDER-PadINT)") (class "Default")
      (node (ref "I/O_EXPANDER") (pin "INT") (pinfunction "INT_INT") (pintype "bidirectional"))
    )
    (net (code "77") (name "unconnected-(I/O_EXPANDER_1-PadINT)") (class "Default")
      (node (ref "I/O_EXPANDER_1") (pin "INT") (pinfunction "INT_INT") (pintype "bidirectional"))
    )
    (net (code "78") (name "unconnected-(I/O_EXPANDER_2-PadINT)") (class "Default")
      (node (ref "I/O_EXPANDER_2") (pin "INT") (pinfunction "INT_INT") (pintype "bidirectional"))
    )
    (net (code "79") (name "unconnected-(I/O_EXPANDER_3-PadINT)") (class "Default")
      (node (ref "I/O_EXPANDER_3") (pin "INT") (pinfunction "INT_INT") (pintype "bidirectional"))
    )
    (net (code "80") (name "unconnected-(I/O_EXPANDER_4-PadINT)") (class "Default")
      (node (ref "I/O_EXPANDER_4") (pin "INT") (pinfunction "INT_INT") (pintype "bidirectional"))
    )
    (net (code "81") (name "unconnected-(I/O_EXPANDER_6-PadINT)") (class "Default")
      (node (ref "I/O_EXPANDER_6") (pin "INT") (pinfunction "INT_INT") (pintype "bidirectional"))
    )
    (net (code "82") (name "unconnected-(U$26-PadINT)") (class "Default")
      (node (ref "U$26") (pin "INT") (pinfunction "INT_INT") (pintype "bidirectional"))
    )
  )
)
